# STM32_Schematic.net
KiCad netlist of a schematic drawn in Altium Designer
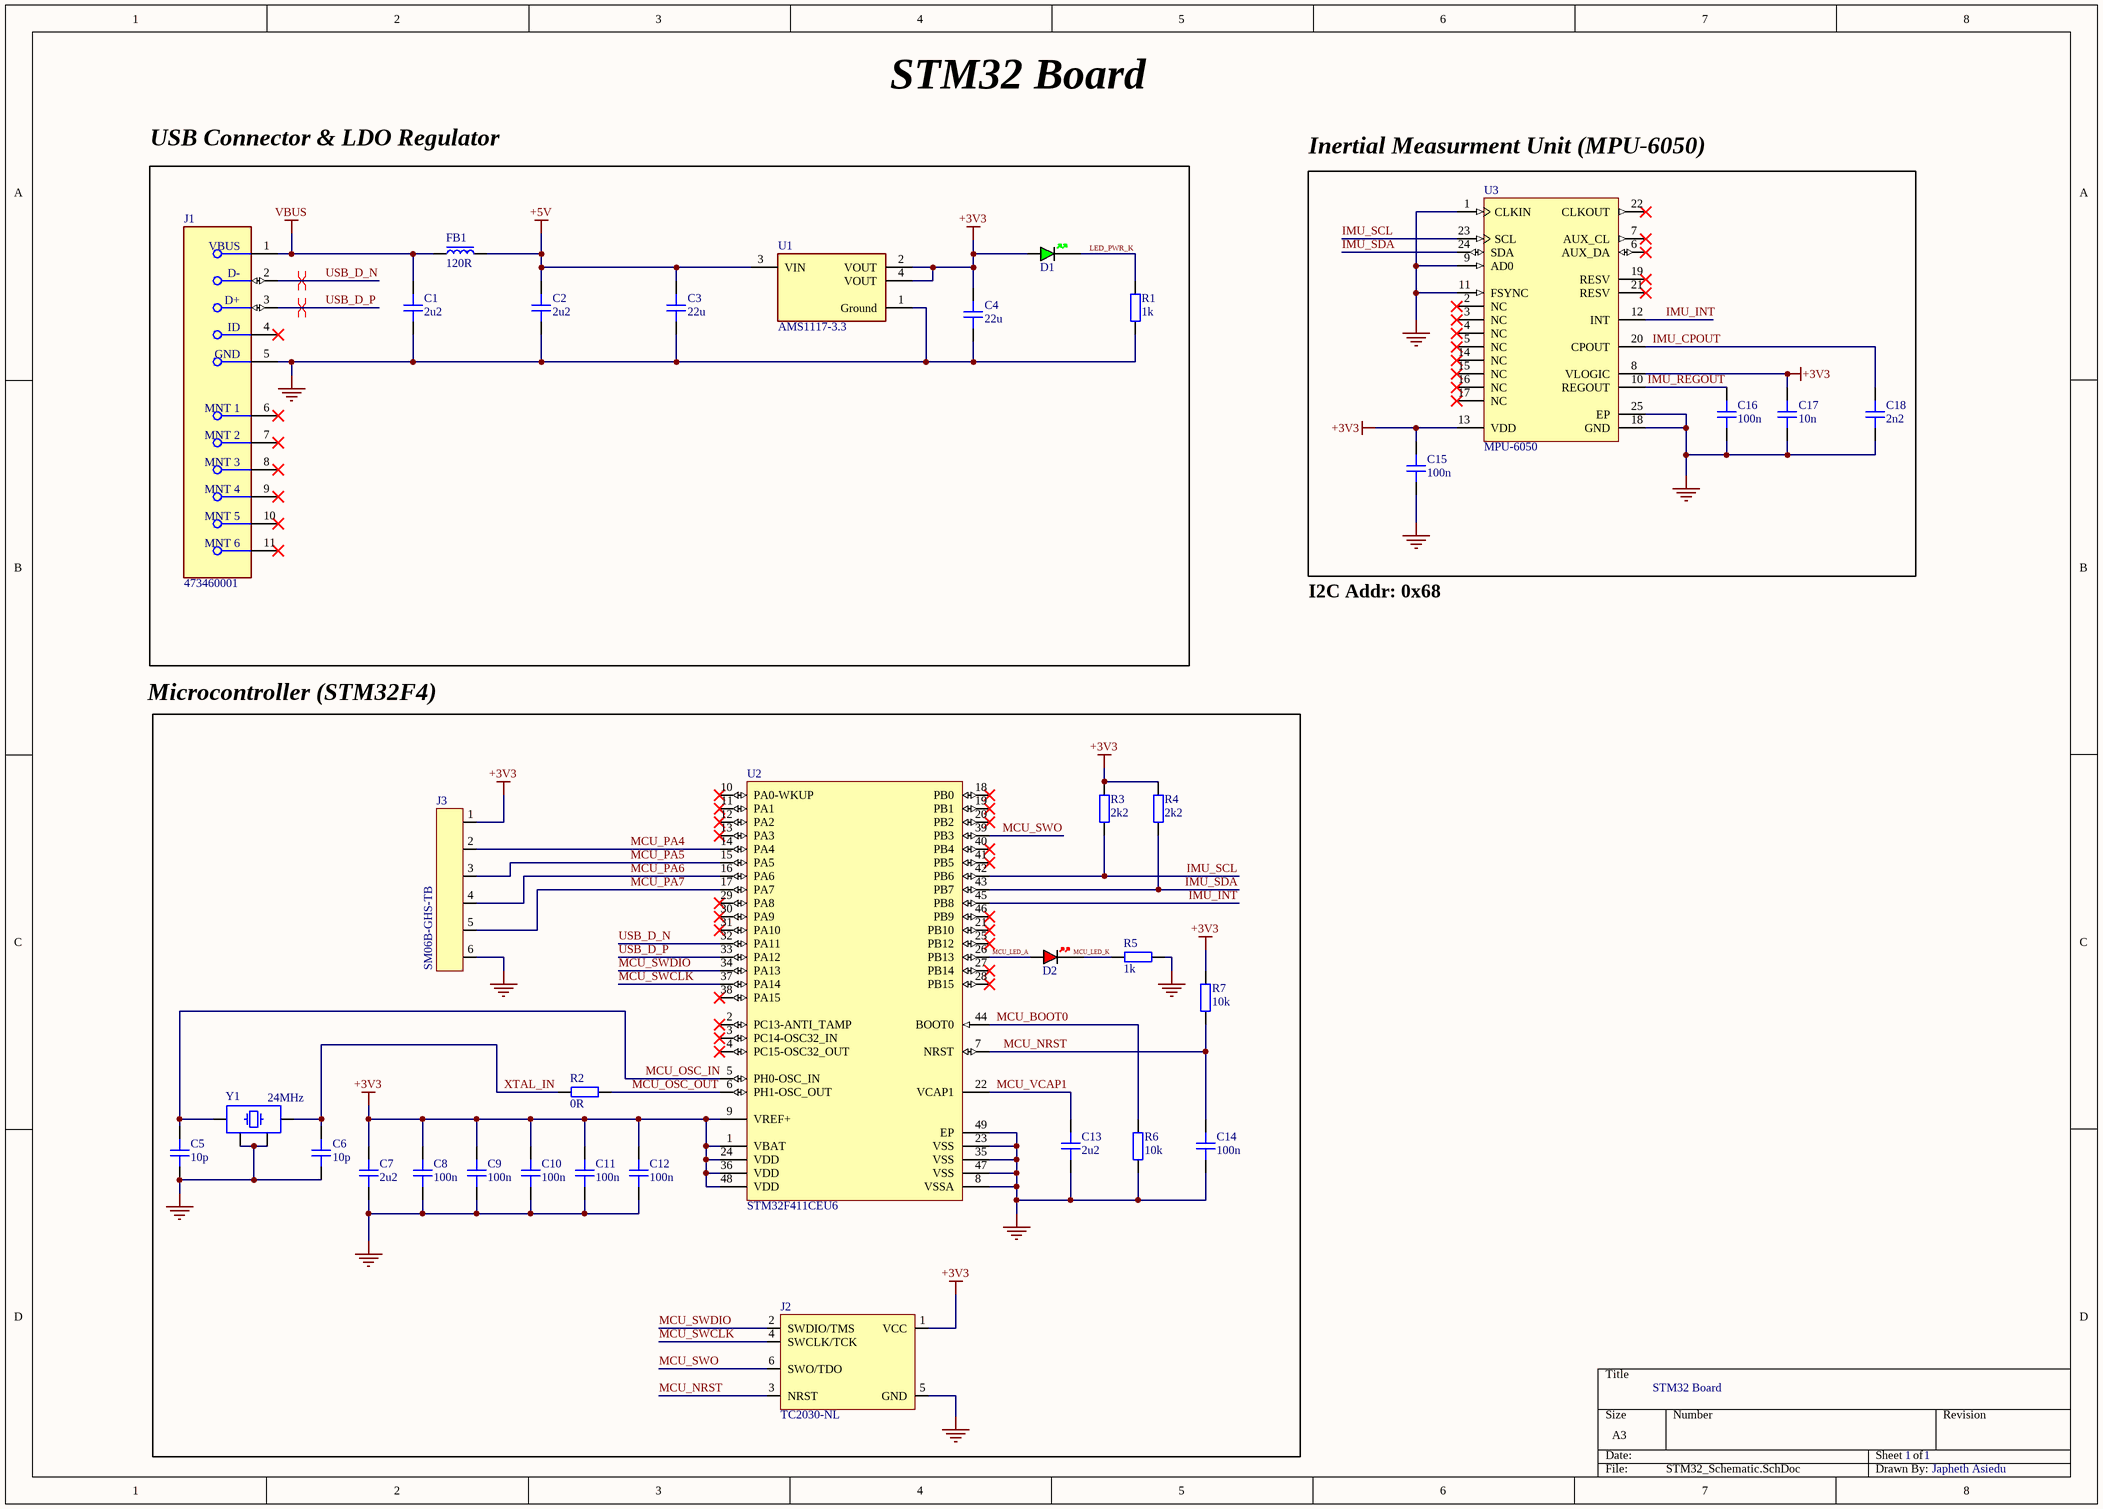
[diagram p0: STM32_Schematic.SchDoc]

(export (version "E")
  (design (tool "Eeschema 10.0.6"))
  (components
    (comp (ref "C1")
      (value "2u2")
      (footprint "CAP_0603")
      (description "Capacitor SMD 0603")
      (libsource (lib "Schematic-Lib-PhilsLab") (part "CAP_0603"))
    )
    (comp (ref "C2")
      (value "2u2")
      (footprint "CAP_0603")
      (description "Capacitor SMD 0603")
      (libsource (lib "Schematic-Lib-PhilsLab") (part "CAP_0603"))
    )
    (comp (ref "C3")
      (value "22u")
      (footprint "CAP_0805")
      (description "Capacitor SMD 0805")
      (libsource (lib "Schematic-Lib-PhilsLab") (part "CAP_0805"))
    )
    (comp (ref "C4")
      (value "22u")
      (footprint "CAP_0805")
      (description "Capacitor SMD 0805")
      (libsource (lib "Schematic-Lib-PhilsLab") (part "CAP_0805"))
    )
    (comp (ref "C5")
      (value "10p")
      (footprint "CAP_0402")
      (description "Capacitor SMD 0402")
      (libsource (lib "Schematic-Lib-PhilsLab") (part "CAP_0402"))
    )
    (comp (ref "C6")
      (value "10p")
      (footprint "CAP_0402")
      (description "Capacitor SMD 0402")
      (libsource (lib "Schematic-Lib-PhilsLab") (part "CAP_0402"))
    )
    (comp (ref "C7")
      (value "2u2")
      (footprint "CAP_0603")
      (description "Capacitor SMD 0603")
      (libsource (lib "Schematic-Lib-PhilsLab") (part "CAP_0603"))
    )
    (comp (ref "C8")
      (value "100n")
      (footprint "CAP_0402")
      (description "Capacitor SMD 0402")
      (libsource (lib "Schematic-Lib-PhilsLab") (part "CAP_0402"))
    )
    (comp (ref "C9")
      (value "100n")
      (footprint "CAP_0402")
      (description "Capacitor SMD 0402")
      (libsource (lib "Schematic-Lib-PhilsLab") (part "CAP_0402"))
    )
    (comp (ref "C10")
      (value "100n")
      (footprint "CAP_0402")
      (description "Capacitor SMD 0402")
      (libsource (lib "Schematic-Lib-PhilsLab") (part "CAP_0402"))
    )
    (comp (ref "C11")
      (value "100n")
      (footprint "CAP_0402")
      (description "Capacitor SMD 0402")
      (libsource (lib "Schematic-Lib-PhilsLab") (part "CAP_0402"))
    )
    (comp (ref "C12")
      (value "100n")
      (footprint "CAP_0402")
      (description "Capacitor SMD 0402")
      (libsource (lib "Schematic-Lib-PhilsLab") (part "CAP_0402"))
    )
    (comp (ref "C13")
      (value "2u2")
      (footprint "CAP_0603")
      (description "Capacitor SMD 0603")
      (libsource (lib "Schematic-Lib-PhilsLab") (part "CAP_0603"))
    )
    (comp (ref "C14")
      (value "100n")
      (footprint "CAP_0402")
      (description "Capacitor SMD 0402")
      (libsource (lib "Schematic-Lib-PhilsLab") (part "CAP_0402"))
    )
    (comp (ref "C15")
      (value "100n")
      (footprint "CAP_0402")
      (description "Capacitor SMD 0402")
      (libsource (lib "Schematic-Lib-PhilsLab") (part "CAP_0402"))
    )
    (comp (ref "C16")
      (value "100n")
      (footprint "CAP_0402")
      (description "Capacitor SMD 0402")
      (libsource (lib "Schematic-Lib-PhilsLab") (part "CAP_0402"))
    )
    (comp (ref "C17")
      (value "10n")
      (footprint "CAP_0402")
      (description "Capacitor SMD 0402")
      (libsource (lib "Schematic-Lib-PhilsLab") (part "CAP_0402"))
    )
    (comp (ref "C18")
      (value "2n2")
      (footprint "CAP_0402")
      (description "Capacitor SMD 0402")
      (libsource (lib "Schematic-Lib-PhilsLab") (part "CAP_0402"))
    )
    (comp (ref "D1")
      (value "GREEN")
      (footprint "LED_0402_GREEN")
      (description "LED 0402 GREEN SMD")
      (libsource (lib "Schematic-Lib-PhilsLab") (part "LED_0402_GREEN"))
    )
    (comp (ref "D2")
      (value "RED")
      (footprint "LED_0402_RED")
      (description "LED 0402 RED SMD")
      (libsource (lib "Schematic-Lib-PhilsLab") (part "LED_0402_RED"))
    )
    (comp (ref "FB1")
      (value "120R")
      (footprint "FB_0603")
      (description "Ferrite Bead SMD 0603")
      (libsource (lib "Schematic-Lib-PhilsLab") (part "FB_0603"))
    )
    (comp (ref "J1")
      (value "473460001")
      (footprint "FP-473460001-MFG")
      (description "CONN RCPT USB2.0 MICRO B SMD R/A")
      (fields
        (field (name "OCTOPART") "https://octopart.com/47346-0001-molex-7164928")
        (field (name "MANUFACTURER") "Molex")
      )
      (libsource (lib "Altium Content Vault") (part "53ae1f1d9b557310b43ca686e5bb76a"))
    )
    (comp (ref "J2")
      (value "TC2030-NL")
      (footprint "TC2030-NL-FP")
      (description "Tag-Connect No-Solder SWD Debug Connector (No Legs) DO NOT PLACE")
      (fields
        (field (name "MANUFACTURER") "Tag-Connect")
        (field (name "MANUFACTURER PART NUMBER") "TC2030-NL-FP")
      )
      (libsource (lib "Schematic-Lib-PhilsLab") (part "TC2030-NL"))
    )
    (comp (ref "J3")
      (value "SM06B-GHS-TB")
      (footprint "SM06B-GHS-TB")
      (description "Header Connector 6 Position 1.25MM Pitch SMD Horizontal JST GH")
      (fields (field (name "MANUFACTURER") "JST"))
      (libsource (lib "Schematic-Lib-PhilsLab") (part "SM06B-GHS-TB"))
    )
    (comp (ref "R1")
      (value "1k")
      (footprint "RES_0402")
      (description "Resistor SMD 0402")
      (libsource (lib "Schematic-Lib-PhilsLab") (part "RES_0402"))
    )
    (comp (ref "R2")
      (value "0R")
      (footprint "RES_0402")
      (description "Resistor SMD 0402")
      (libsource (lib "Schematic-Lib-PhilsLab") (part "RES_0402"))
    )
    (comp (ref "R3")
      (value "2k2")
      (footprint "RES_0402")
      (description "Resistor SMD 0402")
      (libsource (lib "Schematic-Lib-PhilsLab") (part "RES_0402"))
    )
    (comp (ref "R4")
      (value "2k2")
      (footprint "RES_0402")
      (description "Resistor SMD 0402")
      (libsource (lib "Schematic-Lib-PhilsLab") (part "RES_0402"))
    )
    (comp (ref "R5")
      (value "1k")
      (footprint "RES_0402")
      (description "Resistor SMD 0402")
      (libsource (lib "Schematic-Lib-PhilsLab") (part "RES_0402"))
    )
    (comp (ref "R6")
      (value "10k")
      (footprint "RES_0402")
      (description "Resistor SMD 0402")
      (libsource (lib "Schematic-Lib-PhilsLab") (part "RES_0402"))
    )
    (comp (ref "R7")
      (value "10k")
      (footprint "RES_0402")
      (description "Resistor SMD 0402")
      (libsource (lib "Schematic-Lib-PhilsLab") (part "RES_0402"))
    )
    (comp (ref "U1")
      (value "AMS1117-3.3")
      (footprint "FP-AMS1117-IPC_C")
      (description "LDO Voltage Regulators 1A, 3.3V")
      (fields
        (field (name "OCTOPART") "https://octopart.com/ams1117-3.3-advanced+monolithic+systems-25899300")
        (field (name "MANUFACTURER") "Advanced Monolithic Systems")
      )
      (libsource (lib "Altium Content Vault") (part "8bdbb5f8e77002000e30dd2845d0354"))
    )
    (comp (ref "U2")
      (value "STM32F411CEU6")
      (footprint "STM-UFQFPN48_L")
      (libsource (lib "Altium Content Vault") (part "MC-ARM-STM32F411-UFQFPN48"))
    )
    (comp (ref "U3")
      (value "MPU-6050")
      (footprint "IS-QFN-24_V")
      (fields (field (name "MANUFACTURER") "InvenSense"))
      (libsource (lib "Altium Content Vault") (part "IS-MPU-6050-QFN-24"))
    )
    (comp (ref "Y1")
      (value "24MHz")
      (footprint "XTAL_3225")
      (description "Crystal SMD 24MHz 10PPM 7pF 3225")
      (fields
        (field (name "MANUFACTURER") "Epson")
        (field (name "MANUFACTURER PART NUMBER") "TSX-3225 24.0000MF15X-AC")
      )
      (libsource (lib "Schematic-Lib-PhilsLab") (part "TSX-3225_24.0000MF15X-AC"))
    )
  )
  (nets
    (net (code "1") (name "+3V3") (class "Default")
      (node (ref "C10") (pin "2") (pinfunction "2_2") (pintype "passive"))
      (node (ref "C11") (pin "2") (pinfunction "2_2") (pintype "passive"))
      (node (ref "C12") (pin "2") (pinfunction "2_2") (pintype "passive"))
      (node (ref "C15") (pin "2") (pinfunction "2_2") (pintype "passive"))
      (node (ref "C17") (pin "2") (pinfunction "2_2") (pintype "passive"))
      (node (ref "C4") (pin "2") (pinfunction "2_2") (pintype "passive"))
      (node (ref "C7") (pin "1") (pinfunction "1_1") (pintype "passive"))
      (node (ref "C8") (pin "2") (pinfunction "2_2") (pintype "passive"))
      (node (ref "C9") (pin "2") (pinfunction "2_2") (pintype "passive"))
      (node (ref "D1") (pin "A") (pinfunction "A_A") (pintype "passive"))
      (node (ref "J2") (pin "1") (pinfunction "VCC_1") (pintype "passive"))
      (node (ref "J3") (pin "1") (pinfunction "1_1") (pintype "passive"))
      (node (ref "R3") (pin "2") (pinfunction "2_2") (pintype "passive"))
      (node (ref "R4") (pin "2") (pinfunction "2_2") (pintype "passive"))
      (node (ref "R7") (pin "2") (pinfunction "2_2") (pintype "passive"))
      (node (ref "U1") (pin "2") (pinfunction "VOUT_2") (pintype "passive"))
      (node (ref "U1") (pin "4") (pinfunction "VOUT_4") (pintype "passive"))
      (node (ref "U2") (pin "1") (pinfunction "VBAT_1") (pintype "power_in"))
      (node (ref "U2") (pin "24") (pinfunction "VDD_24") (pintype "power_in"))
      (node (ref "U2") (pin "36") (pinfunction "VDD_36") (pintype "power_in"))
      (node (ref "U2") (pin "48") (pinfunction "VDD_48") (pintype "power_in"))
      (node (ref "U2") (pin "9") (pinfunction "VREF+_9") (pintype "power_in"))
      (node (ref "U3") (pin "13") (pinfunction "VDD_13") (pintype "power_in"))
      (node (ref "U3") (pin "8") (pinfunction "VLOGIC_8") (pintype "power_in"))
    )
    (net (code "2") (name "+5V") (class "Default")
      (node (ref "C2") (pin "1") (pinfunction "1_1") (pintype "passive"))
      (node (ref "C3") (pin "2") (pinfunction "2_2") (pintype "passive"))
      (node (ref "FB1") (pin "2") (pinfunction "2_2") (pintype "passive"))
      (node (ref "U1") (pin "3") (pinfunction "VIN_3") (pintype "power_in"))
    )
    (net (code "3") (name "/IMU_CPOUT") (class "Default")
      (node (ref "C18") (pin "2") (pinfunction "2_2") (pintype "passive"))
      (node (ref "U3") (pin "20") (pinfunction "CPOUT_20") (pintype "passive"))
    )
    (net (code "4") (name "/IMU_INT") (class "Default")
      (node (ref "U2") (pin "45") (pinfunction "PB8_45") (pintype "bidirectional"))
      (node (ref "U3") (pin "12") (pinfunction "INT_12") (pintype "open_collector"))
    )
    (net (code "5") (name "/IMU_REGOUT") (class "Default")
      (node (ref "C16") (pin "1") (pinfunction "1_1") (pintype "passive"))
      (node (ref "U3") (pin "10") (pinfunction "REGOUT_10") (pintype "passive"))
    )
    (net (code "6") (name "/IMU_SCL") (class "Default")
      (node (ref "R3") (pin "1") (pinfunction "1_1") (pintype "passive"))
      (node (ref "U2") (pin "42") (pinfunction "PB6_42") (pintype "bidirectional"))
      (node (ref "U3") (pin "23") (pinfunction "SCL_23") (pintype "input"))
    )
    (net (code "7") (name "/IMU_SDA") (class "Default")
      (node (ref "R4") (pin "1") (pinfunction "1_1") (pintype "passive"))
      (node (ref "U2") (pin "43") (pinfunction "PB7_43") (pintype "bidirectional"))
      (node (ref "U3") (pin "24") (pinfunction "SDA_24") (pintype "bidirectional"))
    )
    (net (code "8") (name "/LED_PWR_K") (class "Default")
      (node (ref "D1") (pin "K") (pinfunction "K_K") (pintype "passive"))
      (node (ref "R1") (pin "1") (pinfunction "1_1") (pintype "passive"))
    )
    (net (code "9") (name "/MCU_BOOT0") (class "Default")
      (node (ref "R6") (pin "2") (pinfunction "2_2") (pintype "passive"))
      (node (ref "U2") (pin "44") (pinfunction "BOOT0_44") (pintype "input"))
    )
    (net (code "10") (name "/MCU_LED_A") (class "Default")
      (node (ref "D2") (pin "A") (pinfunction "A_A") (pintype "passive"))
      (node (ref "U2") (pin "26") (pinfunction "PB13_26") (pintype "bidirectional"))
    )
    (net (code "11") (name "/MCU_LED_K") (class "Default")
      (node (ref "D2") (pin "K") (pinfunction "K_K") (pintype "passive"))
      (node (ref "R5") (pin "1") (pinfunction "1_1") (pintype "passive"))
    )
    (net (code "12") (name "/MCU_NRST") (class "Default")
      (node (ref "C14") (pin "2") (pinfunction "2_2") (pintype "passive"))
      (node (ref "J2") (pin "3") (pinfunction "NRST_3") (pintype "passive"))
      (node (ref "R7") (pin "1") (pinfunction "1_1") (pintype "passive"))
      (node (ref "U2") (pin "7") (pinfunction "NRST_7") (pintype "bidirectional"))
    )
    (net (code "13") (name "/MCU_OSC_IN") (class "Default")
      (node (ref "C5") (pin "2") (pinfunction "2_2") (pintype "passive"))
      (node (ref "U2") (pin "5") (pinfunction "PH0-OSC_IN_5") (pintype "bidirectional"))
      (node (ref "Y1") (pin "1") (pinfunction "1_1") (pintype "passive"))
    )
    (net (code "14") (name "/MCU_OSC_OUT") (class "Default")
      (node (ref "R2") (pin "2") (pinfunction "2_2") (pintype "passive"))
      (node (ref "U2") (pin "6") (pinfunction "PH1-OSC_OUT_6") (pintype "bidirectional"))
    )
    (net (code "15") (name "/MCU_PA4") (class "Default")
      (node (ref "J3") (pin "2") (pinfunction "2_2") (pintype "passive"))
      (node (ref "U2") (pin "14") (pinfunction "PA4_14") (pintype "bidirectional"))
    )
    (net (code "16") (name "/MCU_PA5") (class "Default")
      (node (ref "J3") (pin "3") (pinfunction "3_3") (pintype "passive"))
      (node (ref "U2") (pin "15") (pinfunction "PA5_15") (pintype "bidirectional"))
    )
    (net (code "17") (name "/MCU_PA6") (class "Default")
      (node (ref "J3") (pin "4") (pinfunction "4_4") (pintype "passive"))
      (node (ref "U2") (pin "16") (pinfunction "PA6_16") (pintype "bidirectional"))
    )
    (net (code "18") (name "/MCU_PA7") (class "Default")
      (node (ref "J3") (pin "5") (pinfunction "5_5") (pintype "passive"))
      (node (ref "U2") (pin "17") (pinfunction "PA7_17") (pintype "bidirectional"))
    )
    (net (code "19") (name "/MCU_SWCLK") (class "Default")
      (node (ref "J2") (pin "4") (pinfunction "SWCLK/TCK_4") (pintype "passive"))
      (node (ref "U2") (pin "37") (pinfunction "PA14_37") (pintype "bidirectional"))
    )
    (net (code "20") (name "/MCU_SWDIO") (class "Default")
      (node (ref "J2") (pin "2") (pinfunction "SWDIO/TMS_2") (pintype "passive"))
      (node (ref "U2") (pin "34") (pinfunction "PA13_34") (pintype "bidirectional"))
    )
    (net (code "21") (name "/MCU_SWO") (class "Default")
      (node (ref "J2") (pin "6") (pinfunction "SWO/TDO_6") (pintype "passive"))
      (node (ref "U2") (pin "39") (pinfunction "PB3_39") (pintype "bidirectional"))
    )
    (net (code "22") (name "/MCU_VCAP1") (class "Default")
      (node (ref "C13") (pin "1") (pinfunction "1_1") (pintype "passive"))
      (node (ref "U2") (pin "22") (pinfunction "VCAP1_22") (pintype "passive"))
    )
    (net (code "23") (name "/USB_D_N") (class "Default")
      (node (ref "J1") (pin "2") (pinfunction "D-_2") (pintype "bidirectional"))
      (node (ref "U2") (pin "32") (pinfunction "PA11_32") (pintype "bidirectional"))
    )
    (net (code "24") (name "/USB_D_P") (class "Default")
      (node (ref "J1") (pin "3") (pinfunction "D+_3") (pintype "bidirectional"))
      (node (ref "U2") (pin "33") (pinfunction "PA12_33") (pintype "bidirectional"))
    )
    (net (code "25") (name "/XTAL_IN") (class "Default")
      (node (ref "C6") (pin "2") (pinfunction "2_2") (pintype "passive"))
      (node (ref "R2") (pin "1") (pinfunction "1_1") (pintype "passive"))
      (node (ref "Y1") (pin "3") (pinfunction "3_3") (pintype "passive"))
    )
    (net (code "26") (name "GND") (class "Default")
      (node (ref "C1") (pin "2") (pinfunction "2_2") (pintype "passive"))
      (node (ref "C10") (pin "1") (pinfunction "1_1") (pintype "passive"))
      (node (ref "C11") (pin "1") (pinfunction "1_1") (pintype "passive"))
      (node (ref "C12") (pin "1") (pinfunction "1_1") (pintype "passive"))
      (node (ref "C13") (pin "2") (pinfunction "2_2") (pintype "passive"))
      (node (ref "C14") (pin "1") (pinfunction "1_1") (pintype "passive"))
      (node (ref "C15") (pin "1") (pinfunction "1_1") (pintype "passive"))
      (node (ref "C16") (pin "2") (pinfunction "2_2") (pintype "passive"))
      (node (ref "C17") (pin "1") (pinfunction "1_1") (pintype "passive"))
      (node (ref "C18") (pin "1") (pinfunction "1_1") (pintype "passive"))
      (node (ref "C2") (pin "2") (pinfunction "2_2") (pintype "passive"))
      (node (ref "C3") (pin "1") (pinfunction "1_1") (pintype "passive"))
      (node (ref "C4") (pin "1") (pinfunction "1_1") (pintype "passive"))
      (node (ref "C5") (pin "1") (pinfunction "1_1") (pintype "passive"))
      (node (ref "C6") (pin "1") (pinfunction "1_1") (pintype "passive"))
      (node (ref "C7") (pin "2") (pinfunction "2_2") (pintype "passive"))
      (node (ref "C8") (pin "1") (pinfunction "1_1") (pintype "passive"))
      (node (ref "C9") (pin "1") (pinfunction "1_1") (pintype "passive"))
      (node (ref "J1") (pin "5") (pinfunction "GND_5") (pintype "power_in"))
      (node (ref "J2") (pin "5") (pinfunction "GND_5") (pintype "passive"))
      (node (ref "J3") (pin "6") (pinfunction "6_6") (pintype "passive"))
      (node (ref "R1") (pin "2") (pinfunction "2_2") (pintype "passive"))
      (node (ref "R5") (pin "2") (pinfunction "2_2") (pintype "passive"))
      (node (ref "R6") (pin "1") (pinfunction "1_1") (pintype "passive"))
      (node (ref "U1") (pin "1") (pinfunction "Ground_1") (pintype "power_in"))
      (node (ref "U2") (pin "23") (pinfunction "VSS_23") (pintype "power_in"))
      (node (ref "U2") (pin "35") (pinfunction "VSS_35") (pintype "power_in"))
      (node (ref "U2") (pin "47") (pinfunction "VSS_47") (pintype "power_in"))
      (node (ref "U2") (pin "49") (pinfunction "EP_49") (pintype "power_in"))
      (node (ref "U2") (pin "8") (pinfunction "VSSA_8") (pintype "power_in"))
      (node (ref "U3") (pin "1") (pinfunction "CLKIN_1") (pintype "input"))
      (node (ref "U3") (pin "11") (pinfunction "FSYNC_11") (pintype "input"))
      (node (ref "U3") (pin "18") (pinfunction "GND_18") (pintype "power_in"))
      (node (ref "U3") (pin "25") (pinfunction "EP_25") (pintype "power_in"))
      (node (ref "U3") (pin "9") (pinfunction "AD0_9") (pintype "input"))
      (node (ref "Y1") (pin "2") (pinfunction "2_2") (pintype "passive"))
      (node (ref "Y1") (pin "4") (pinfunction "4_4") (pintype "passive"))
    )
    (net (code "27") (name "VBUS") (class "Default")
      (node (ref "C1") (pin "1") (pinfunction "1_1") (pintype "passive"))
      (node (ref "FB1") (pin "1") (pinfunction "1_1") (pintype "passive"))
      (node (ref "J1") (pin "1") (pinfunction "VBUS_1") (pintype "power_in"))
    )
    (net (code "28") (name "unconnected-(J1-ID-Pad4)") (class "Default")
      (node (ref "J1") (pin "4") (pinfunction "ID_4") (pintype "passive+no_connect"))
    )
    (net (code "29") (name "unconnected-(J1-MNT_1-Pad6)") (class "Default")
      (node (ref "J1") (pin "6") (pinfunction "MNT_1_6") (pintype "passive+no_connect"))
    )
    (net (code "30") (name "unconnected-(J1-MNT_2-Pad7)") (class "Default")
      (node (ref "J1") (pin "7") (pinfunction "MNT_2_7") (pintype "passive+no_connect"))
    )
    (net (code "31") (name "unconnected-(J1-MNT_3-Pad8)") (class "Default")
      (node (ref "J1") (pin "8") (pinfunction "MNT_3_8") (pintype "passive+no_connect"))
    )
    (net (code "32") (name "unconnected-(J1-MNT_4-Pad9)") (class "Default")
      (node (ref "J1") (pin "9") (pinfunction "MNT_4_9") (pintype "passive+no_connect"))
    )
    (net (code "33") (name "unconnected-(J1-MNT_5-Pad10)") (class "Default")
      (node (ref "J1") (pin "10") (pinfunction "MNT_5_10") (pintype "passive+no_connect"))
    )
    (net (code "34") (name "unconnected-(J1-MNT_6-Pad11)") (class "Default")
      (node (ref "J1") (pin "11") (pinfunction "MNT_6_11") (pintype "passive+no_connect"))
    )
    (net (code "35") (name "unconnected-(U2-PA0-WKUP-Pad10)") (class "Default")
      (node (ref "U2") (pin "10") (pinfunction "PA0-WKUP_10") (pintype "bidirectional+no_connect"))
    )
    (net (code "36") (name "unconnected-(U2-PA1-Pad11)") (class "Default")
      (node (ref "U2") (pin "11") (pinfunction "PA1_11") (pintype "bidirectional+no_connect"))
    )
    (net (code "37") (name "unconnected-(U2-PA2-Pad12)") (class "Default")
      (node (ref "U2") (pin "12") (pinfunction "PA2_12") (pintype "bidirectional+no_connect"))
    )
    (net (code "38") (name "unconnected-(U2-PA3-Pad13)") (class "Default")
      (node (ref "U2") (pin "13") (pinfunction "PA3_13") (pintype "bidirectional+no_connect"))
    )
    (net (code "39") (name "unconnected-(U2-PA8-Pad29)") (class "Default")
      (node (ref "U2") (pin "29") (pinfunction "PA8_29") (pintype "bidirectional+no_connect"))
    )
    (net (code "40") (name "unconnected-(U2-PA9-Pad30)") (class "Default")
      (node (ref "U2") (pin "30") (pinfunction "PA9_30") (pintype "bidirectional+no_connect"))
    )
    (net (code "41") (name "unconnected-(U2-PA10-Pad31)") (class "Default")
      (node (ref "U2") (pin "31") (pinfunction "PA10_31") (pintype "bidirectional+no_connect"))
    )
    (net (code "42") (name "unconnected-(U2-PA15-Pad38)") (class "Default")
      (node (ref "U2") (pin "38") (pinfunction "PA15_38") (pintype "bidirectional+no_connect"))
    )
    (net (code "43") (name "unconnected-(U2-PB0-Pad18)") (class "Default")
      (node (ref "U2") (pin "18") (pinfunction "PB0_18") (pintype "bidirectional+no_connect"))
    )
    (net (code "44") (name "unconnected-(U2-PB1-Pad19)") (class "Default")
      (node (ref "U2") (pin "19") (pinfunction "PB1_19") (pintype "bidirectional+no_connect"))
    )
    (net (code "45") (name "unconnected-(U2-PB2-Pad20)") (class "Default")
      (node (ref "U2") (pin "20") (pinfunction "PB2_20") (pintype "bidirectional+no_connect"))
    )
    (net (code "46") (name "unconnected-(U2-PB4-Pad40)") (class "Default")
      (node (ref "U2") (pin "40") (pinfunction "PB4_40") (pintype "bidirectional+no_connect"))
    )
    (net (code "47") (name "unconnected-(U2-PB5-Pad41)") (class "Default")
      (node (ref "U2") (pin "41") (pinfunction "PB5_41") (pintype "bidirectional+no_connect"))
    )
    (net (code "48") (name "unconnected-(U2-PB9-Pad46)") (class "Default")
      (node (ref "U2") (pin "46") (pinfunction "PB9_46") (pintype "bidirectional+no_connect"))
    )
    (net (code "49") (name "unconnected-(U2-PB10-Pad21)") (class "Default")
      (node (ref "U2") (pin "21") (pinfunction "PB10_21") (pintype "bidirectional+no_connect"))
    )
    (net (code "50") (name "unconnected-(U2-PB12-Pad25)") (class "Default")
      (node (ref "U2") (pin "25") (pinfunction "PB12_25") (pintype "bidirectional+no_connect"))
    )
    (net (code "51") (name "unconnected-(U2-PB14-Pad27)") (class "Default")
      (node (ref "U2") (pin "27") (pinfunction "PB14_27") (pintype "bidirectional+no_connect"))
    )
    (net (code "52") (name "unconnected-(U2-PB15-Pad28)") (class "Default")
      (node (ref "U2") (pin "28") (pinfunction "PB15_28") (pintype "bidirectional+no_connect"))
    )
    (net (code "53") (name "unconnected-(U2-PC13-ANTI_TAMP-Pad2)") (class "Default")
      (node (ref "U2") (pin "2") (pinfunction "PC13-ANTI_TAMP_2") (pintype "bidirectional+no_connect"))
    )
    (net (code "54") (name "unconnected-(U2-PC14-OSC32_IN-Pad3)") (class "Default")
      (node (ref "U2") (pin "3") (pinfunction "PC14-OSC32_IN_3") (pintype "bidirectional+no_connect"))
    )
    (net (code "55") (name "unconnected-(U2-PC15-OSC32_OUT-Pad4)") (class "Default")
      (node (ref "U2") (pin "4") (pinfunction "PC15-OSC32_OUT_4") (pintype "bidirectional+no_connect"))
    )
    (net (code "56") (name "unconnected-(U3-AUX_CL-Pad7)") (class "Default")
      (node (ref "U3") (pin "7") (pinfunction "AUX_CL_7") (pintype "output+no_connect"))
    )
    (net (code "57") (name "unconnected-(U3-AUX_DA-Pad6)") (class "Default")
      (node (ref "U3") (pin "6") (pinfunction "AUX_DA_6") (pintype "bidirectional+no_connect"))
    )
    (net (code "58") (name "unconnected-(U3-CLKOUT-Pad22)") (class "Default")
      (node (ref "U3") (pin "22") (pinfunction "CLKOUT_22") (pintype "output+no_connect"))
    )
    (net (code "59") (name "unconnected-(U3-NC-Pad2)") (class "Default")
      (node (ref "U3") (pin "2") (pinfunction "NC_2") (pintype "passive+no_connect"))
    )
    (net (code "60") (name "unconnected-(U3-NC-Pad3)") (class "Default")
      (node (ref "U3") (pin "3") (pinfunction "NC_3") (pintype "passive+no_connect"))
    )
    (net (code "61") (name "unconnected-(U3-NC-Pad4)") (class "Default")
      (node (ref "U3") (pin "4") (pinfunction "NC_4") (pintype "passive+no_connect"))
    )
    (net (code "62") (name "unconnected-(U3-NC-Pad5)") (class "Default")
      (node (ref "U3") (pin "5") (pinfunction "NC_5") (pintype "passive+no_connect"))
    )
    (net (code "63") (name "unconnected-(U3-NC-Pad14)") (class "Default")
      (node (ref "U3") (pin "14") (pinfunction "NC_14") (pintype "passive+no_connect"))
    )
    (net (code "64") (name "unconnected-(U3-NC-Pad15)") (class "Default")
      (node (ref "U3") (pin "15") (pinfunction "NC_15") (pintype "passive+no_connect"))
    )
    (net (code "65") (name "unconnected-(U3-NC-Pad16)") (class "Default")
      (node (ref "U3") (pin "16") (pinfunction "NC_16") (pintype "passive+no_connect"))
    )
    (net (code "66") (name "unconnected-(U3-NC-Pad17)") (class "Default")
      (node (ref "U3") (pin "17") (pinfunction "NC_17") (pintype "passive+no_connect"))
    )
    (net (code "67") (name "unconnected-(U3-RESV-Pad19)") (class "Default")
      (node (ref "U3") (pin "19") (pinfunction "RESV_19") (pintype "passive+no_connect"))
    )
    (net (code "68") (name "unconnected-(U3-RESV-Pad21)") (class "Default")
      (node (ref "U3") (pin "21") (pinfunction "RESV_21") (pintype "passive+no_connect"))
    )
  )
)
